# 5v_dcdc_blk.net
KiCad netlist of a schematic drawn in Altium Designer
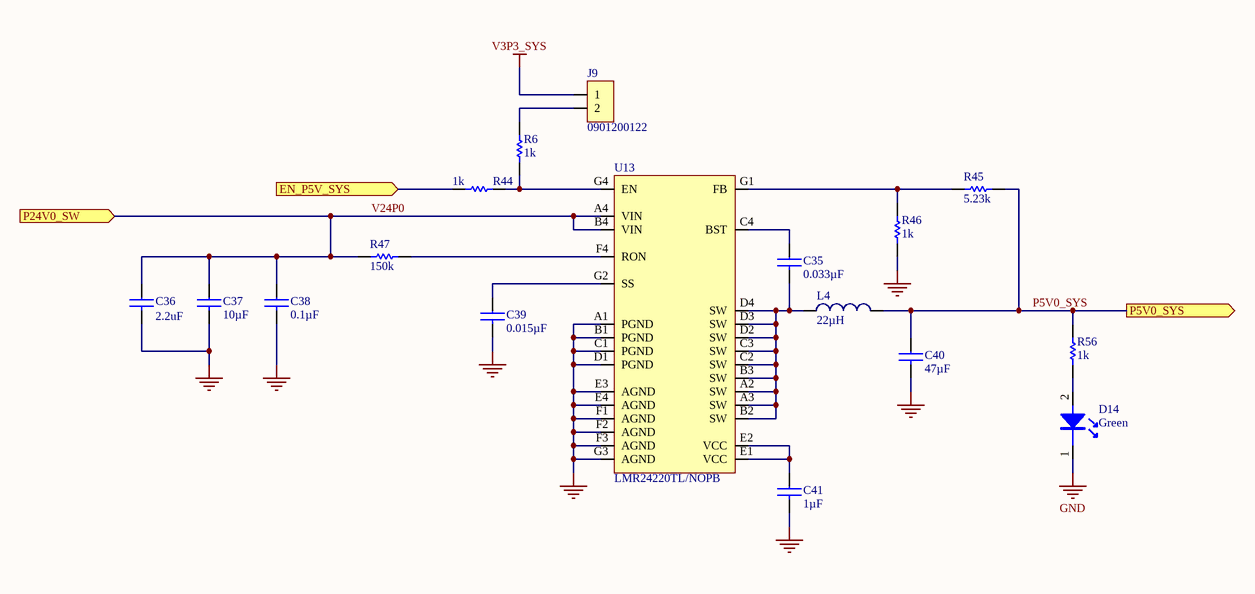
[diagram p0: 5v_dcdc_blk.SchDoc]

(export (version "E")
  (design (tool "Eeschema 10.0.6"))
  (components
    (comp (ref "C35")
      (value "0.033µF")
      (footprint "C0402")
      (description "CAP CER 0.033UF 25V X7R 0402")
      (fields (field (name "MPN") "GRM155R71E333KA88D"))
      (libsource (lib "Capacitor") (part "GRM155R71E333KA88D"))
    )
    (comp (ref "C36")
      (value "2.2uF")
      (footprint "C0603")
      (description "CAP CER 2.2UF 35V X5R 0603")
      (fields (field (name "MPN") "C1608X5R1V225K080AC"))
      (libsource (lib "Capacitor") (part "C1608X5R1V225K080AC"))
    )
    (comp (ref "C37")
      (value "10µF")
      (footprint "C1210")
      (description "CAP CER 10UF 35V X7R 1210")
      (fields (field (name "MPN") "GRM32ER7YA106KA12L"))
      (libsource (lib "Capacitor") (part "GRM32ER7YA106KA12L"))
    )
    (comp (ref "C38")
      (value "0.1µF")
      (footprint "C0805")
      (description "CAP CER 0.1UF 50V X7R 0805")
      (fields (field (name "MPN") "C0805C104K5RACTU"))
      (libsource (lib "Capacitor") (part "C0805C104K5RACTU"))
    )
    (comp (ref "C39")
      (value "0.015µF")
      (footprint "C0402")
      (description "CAP CER 0.015UF 25V X7R 0402")
      (fields (field (name "MPN") "GRM155R71E153KA61D"))
      (libsource (lib "Capacitor") (part "GRM155R71E153KA61D"))
    )
    (comp (ref "C40")
      (value "47µF")
      (footprint "C1206")
      (description "CAP CER 47UF 10V X5R 1206")
      (fields (field (name "MPN") "GRM31CR61A476KE15L"))
      (libsource (lib "Capacitor") (part "GRM31CR61A476KE15L"))
    )
    (comp (ref "C41")
      (value "1µF")
      (footprint "C0603")
      (description "CAP CER 1UF 25V X5R 0603")
      (fields (field (name "MPN") "GRM188R61E105KA12D"))
      (libsource (lib "Capacitor") (part "GRM188R61E105KA12D"))
    )
    (comp (ref "D14")
      (value "Green")
      (footprint "LED0402(GREEN)")
      (description "LED GREEN 0402 SMD")
      (fields (field (name "MPN") "LNJ347W83RA"))
      (libsource (lib "Diode") (part "LNJ347W83RA"))
    )
    (comp (ref "J9")
      (value "*")
      (footprint "0901200122")
      (description "CONN HEADER 2POS .100\" STR TIN")
      (fields (field (name "MPN") "0901200122"))
      (libsource (lib "Connector") (part "0901200122"))
    )
    (comp (ref "L4")
      (value "22µH")
      (footprint "MPI4040R3-220-R")
      (description "FIXED IND 22UH 1.1A 408 MOHM SMD")
      (fields (field (name "MPN") "MPI4040R3-220-R"))
      (libsource (lib "Inductor") (part "MPI4040R3-220-R"))
    )
    (comp (ref "R6")
      (value "1k")
      (footprint "R0603")
      (description "RES SMD 1K OHM 1% 1/16W 0603")
      (fields (field (name "MPN") "6-1879336-2"))
      (libsource (lib "Res") (part "6-1879336-2"))
    )
    (comp (ref "R44")
      (value "1k")
      (footprint "R0402")
      (description "RES SMD 1K OHM 1% 1/16W 0402")
      (fields (field (name "MPN") "CRCW04021K00FKED"))
      (libsource (lib "Res") (part "CRCW04021K00FKED"))
    )
    (comp (ref "R45")
      (value "5.23k")
      (footprint "R0402")
      (description "RES SMD 5.23K OHM 1% 1/16W 0402")
      (fields (field (name "MPN") "CRCW04025K23FKED"))
      (libsource (lib "Res") (part "CRCW04025K23FKED"))
    )
    (comp (ref "R46")
      (value "1k")
      (footprint "R0402")
      (description "RES SMD 1K OHM 1% 1/16W 0402")
      (fields (field (name "MPN") "CRCW04021K00FKED"))
      (libsource (lib "Res") (part "CRCW04021K00FKED"))
    )
    (comp (ref "R47")
      (value "150k")
      (footprint "R0402")
      (description "RES SMD 150K OHM 1% 1/16W 0402")
      (fields (field (name "MPN") "CRCW0402150KFKED"))
      (libsource (lib "Res") (part "CRCW0402150KFKED"))
    )
    (comp (ref "R56")
      (value "1k")
      (footprint "R0603")
      (description "RES SMD 1K OHM 1% 1/10W 0603")
      (fields (field (name "MPN") "ERJ-3EKF1001V"))
      (libsource (lib "Res") (part "ERJ-3EKF1001V"))
    )
    (comp (ref "U13")
      (value "*")
      (footprint "DSBGA-28")
      (description "Voltage Regulators - Switching Regulators 42VIN,2A SIMPLE SW NANO STEP-DOWN REG")
      (fields (field (name "MPN") "LMR24220TL/NOPB"))
      (libsource (lib "IC") (part "LMR24220TL/NOPB"))
    )
  )
  (nets
    (net (code "1") (name "/EN_P5V_SYS") (class "Default")
      (node (ref "R44") (pin "2") (pinfunction "2_2") (pintype "passive"))
    )
    (net (code "2") (name "/P5V0_SYS") (class "Default")
      (node (ref "C40") (pin "1") (pinfunction "1_1") (pintype "passive"))
      (node (ref "L4") (pin "1") (pinfunction "1_1") (pintype "passive"))
      (node (ref "R45") (pin "1") (pinfunction "1_1") (pintype "passive"))
      (node (ref "R56") (pin "2") (pinfunction "2_2") (pintype "passive"))
    )
    (net (code "3") (name "/V24P0") (class "Default")
      (node (ref "C36") (pin "1") (pinfunction "1_1") (pintype "passive"))
      (node (ref "C37") (pin "1") (pinfunction "1_1") (pintype "passive"))
      (node (ref "C38") (pin "1") (pinfunction "1_1") (pintype "passive"))
      (node (ref "R47") (pin "2") (pinfunction "2_2") (pintype "passive"))
      (node (ref "U13") (pin "A4") (pinfunction "VIN_A4") (pintype "passive"))
      (node (ref "U13") (pin "B4") (pinfunction "VIN_B4") (pintype "passive"))
    )
    (net (code "4") (name "GND") (class "Default")
      (node (ref "C36") (pin "2") (pinfunction "2_2") (pintype "passive"))
      (node (ref "C37") (pin "2") (pinfunction "2_2") (pintype "passive"))
      (node (ref "C38") (pin "2") (pinfunction "2_2") (pintype "passive"))
      (node (ref "C39") (pin "2") (pinfunction "2_2") (pintype "passive"))
      (node (ref "C40") (pin "2") (pinfunction "2_2") (pintype "passive"))
      (node (ref "C41") (pin "2") (pinfunction "2_2") (pintype "passive"))
      (node (ref "D14") (pin "1") (pinfunction "1_1") (pintype "passive"))
      (node (ref "R46") (pin "2") (pinfunction "2_2") (pintype "passive"))
      (node (ref "U13") (pin "A1") (pinfunction "PGND_A1") (pintype "passive"))
      (node (ref "U13") (pin "B1") (pinfunction "PGND_B1") (pintype "passive"))
      (node (ref "U13") (pin "C1") (pinfunction "PGND_C1") (pintype "passive"))
      (node (ref "U13") (pin "D1") (pinfunction "PGND_D1") (pintype "passive"))
      (node (ref "U13") (pin "E3") (pinfunction "AGND_E3") (pintype "passive"))
      (node (ref "U13") (pin "E4") (pinfunction "AGND_E4") (pintype "passive"))
      (node (ref "U13") (pin "F1") (pinfunction "AGND_F1") (pintype "passive"))
      (node (ref "U13") (pin "F2") (pinfunction "AGND_F2") (pintype "passive"))
      (node (ref "U13") (pin "F3") (pinfunction "AGND_F3") (pintype "passive"))
      (node (ref "U13") (pin "G3") (pinfunction "AGND_G3") (pintype "passive"))
    )
    (net (code "5") (name "Net-(C35-Pad2)") (class "Default")
      (node (ref "C35") (pin "2") (pinfunction "2_2") (pintype "passive"))
      (node (ref "L4") (pin "2") (pinfunction "2_2") (pintype "passive"))
      (node (ref "U13") (pin "A2") (pinfunction "SW_A2") (pintype "passive"))
      (node (ref "U13") (pin "A3") (pinfunction "SW_A3") (pintype "passive"))
      (node (ref "U13") (pin "B2") (pinfunction "SW_B2") (pintype "passive"))
      (node (ref "U13") (pin "B3") (pinfunction "SW_B3") (pintype "passive"))
      (node (ref "U13") (pin "C2") (pinfunction "SW_C2") (pintype "passive"))
      (node (ref "U13") (pin "C3") (pinfunction "SW_C3") (pintype "passive"))
      (node (ref "U13") (pin "D2") (pinfunction "SW_D2") (pintype "passive"))
      (node (ref "U13") (pin "D3") (pinfunction "SW_D3") (pintype "passive"))
      (node (ref "U13") (pin "D4") (pinfunction "SW_D4") (pintype "passive"))
    )
    (net (code "6") (name "Net-(C41-Pad1)") (class "Default")
      (node (ref "C41") (pin "1") (pinfunction "1_1") (pintype "passive"))
      (node (ref "U13") (pin "E1") (pinfunction "VCC_E1") (pintype "passive"))
      (node (ref "U13") (pin "E2") (pinfunction "VCC_E2") (pintype "passive"))
    )
    (net (code "7") (name "Net-(D14-Pad2)") (class "Default")
      (node (ref "D14") (pin "2") (pinfunction "2_2") (pintype "passive"))
      (node (ref "R56") (pin "1") (pinfunction "1_1") (pintype "passive"))
    )
    (net (code "8") (name "Net-(J9-Pad2)") (class "Default")
      (node (ref "J9") (pin "2") (pinfunction "2_2") (pintype "passive"))
      (node (ref "R6") (pin "2") (pinfunction "2_2") (pintype "passive"))
    )
    (net (code "9") (name "Net-(U13-BST)") (class "Default")
      (node (ref "C35") (pin "1") (pinfunction "1_1") (pintype "passive"))
      (node (ref "U13") (pin "C4") (pinfunction "BST_C4") (pintype "passive"))
    )
    (net (code "10") (name "Net-(U13-EN)") (class "Default")
      (node (ref "R44") (pin "1") (pinfunction "1_1") (pintype "passive"))
      (node (ref "R6") (pin "1") (pinfunction "1_1") (pintype "passive"))
      (node (ref "U13") (pin "G4") (pinfunction "EN_G4") (pintype "passive"))
    )
    (net (code "11") (name "Net-(U13-FB)") (class "Default")
      (node (ref "R45") (pin "2") (pinfunction "2_2") (pintype "passive"))
      (node (ref "R46") (pin "1") (pinfunction "1_1") (pintype "passive"))
      (node (ref "U13") (pin "G1") (pinfunction "FB_G1") (pintype "passive"))
    )
    (net (code "12") (name "Net-(U13-RON)") (class "Default")
      (node (ref "R47") (pin "1") (pinfunction "1_1") (pintype "passive"))
      (node (ref "U13") (pin "F4") (pinfunction "RON_F4") (pintype "passive"))
    )
    (net (code "13") (name "Net-(U13-SS)") (class "Default")
      (node (ref "C39") (pin "1") (pinfunction "1_1") (pintype "passive"))
      (node (ref "U13") (pin "G2") (pinfunction "SS_G2") (pintype "passive"))
    )
    (net (code "14") (name "V3P3_SYS") (class "Default")
      (node (ref "J9") (pin "1") (pinfunction "1_1") (pintype "passive"))
    )
  )
)
